# Ryan-Flashlight.net
KiCad netlist of a schematic drawn in EAGLE
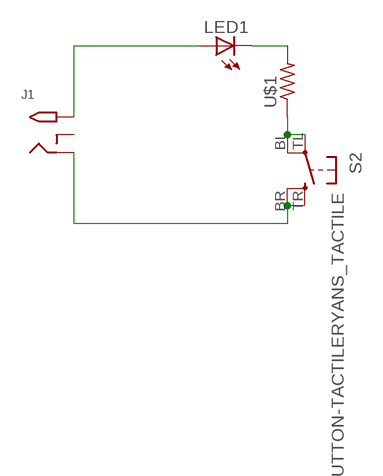
[diagram p0: schematic, sheet 1]

(export (version "E")
  (design (tool "Eeschema 10.0.6"))
  (components
    (comp (ref "J1")
      (value "2.1MMJACKTHM")
      (footprint "eagle-import:PJ-102A")
      (libsource (lib "eagle-import") (part "2.1MMJACKTHM"))
    )
    (comp (ref "LED1")
      (value "LED5MM")
      (footprint "eagle-import:LED5MM")
      (libsource (lib "eagle-import") (part "LED5MM"))
    )
    (comp (ref "S2")
      (value "BUTTON-TACTILERYANS_TACTILE")
      (footprint "eagle-import:TACTILE_1")
      (libsource (lib "eagle-import") (part "BUTTON-TACTILERYANS_TACTILE"))
    )
    (comp (ref "U$1")
      (value "RESISTORTH-1/4W-CARBON")
      (footprint "eagle-import:RESAD1160W55L680D260_HS")
      (libsource (lib "eagle-import") (part "RESISTORTH-1/4W-CARBON"))
    )
  )
  (nets
    (net (code "1") (name "Net-(J1-PadTIP)") (class "Default")
      (node (ref "J1") (pin "TIP") (pinfunction "TIP_TIP") (pintype "bidirectional"))
      (node (ref "LED1") (pin "A") (pinfunction "A_A") (pintype "passive"))
    )
    (net (code "2") (name "Net-(LED1-C)") (class "Default")
      (node (ref "LED1") (pin "K") (pinfunction "C_K") (pintype "passive"))
      (node (ref "U$1") (pin "2") (pinfunction "2_2") (pintype "passive"))
    )
    (net (code "3") (name "Net-(S2-P)") (class "Default")
      (node (ref "S2") (pin "BL") (pinfunction "P1_BL") (pintype "passive"))
      (node (ref "S2") (pin "TL") (pinfunction "P_TL") (pintype "passive"))
      (node (ref "U$1") (pin "1") (pinfunction "1_1") (pintype "passive"))
    )
    (net (code "4") (name "Net-(S2-S)") (class "Default")
      (node (ref "J1") (pin "RING") (pinfunction "RING_RING") (pintype "bidirectional"))
      (node (ref "S2") (pin "BR") (pinfunction "S1_BR") (pintype "passive"))
      (node (ref "S2") (pin "TR") (pinfunction "S_TR") (pintype "passive"))
    )
    (net (code "5") (name "unconnected-(J1-PadRING_SW)") (class "Default")
      (node (ref "J1") (pin "RING_SW") (pinfunction "RING_SW_RING_SW") (pintype "bidirectional"))
    )
  )
)
